# simplePDschematicsv1.net
KiCad netlist of a schematic drawn in EAGLE
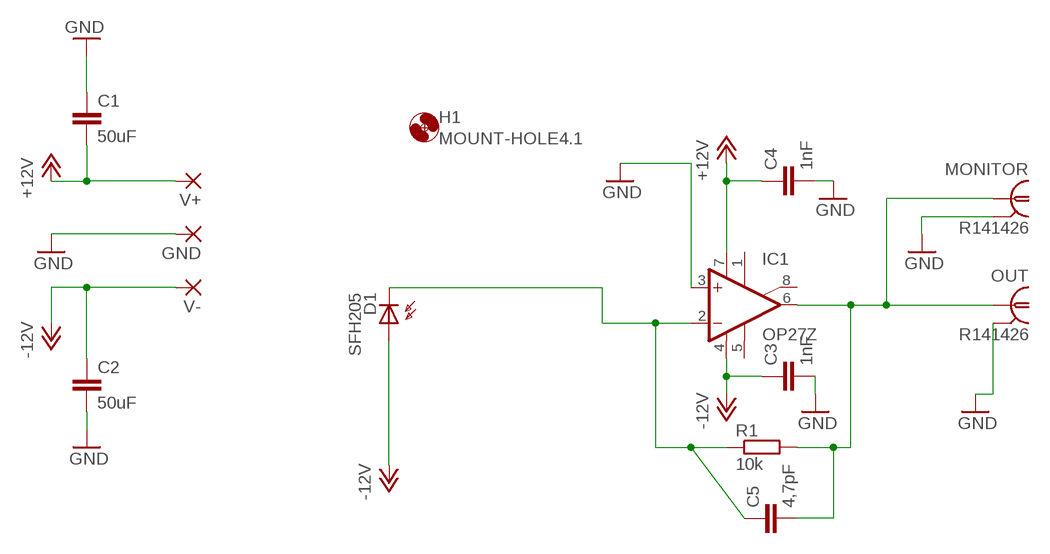
[diagram p0: schematic, sheet 1]

(export (version "E")
  (design (tool "Eeschema 10.0.6"))
  (components
    (comp (ref "C1")
      (value "50uF")
      (footprint "eagle-import:C025-050X050")
      (libsource (lib "eagle-import") (part "C-EU025-050X050"))
    )
    (comp (ref "C2")
      (value "50uF")
      (footprint "eagle-import:C025-050X050")
      (libsource (lib "eagle-import") (part "C-EU025-050X050"))
    )
    (comp (ref "C3")
      (value "1nF")
      (footprint "eagle-import:C025-050X050")
      (libsource (lib "eagle-import") (part "C-EU025-050X050"))
    )
    (comp (ref "C4")
      (value "1nF")
      (footprint "eagle-import:C025-050X050")
      (libsource (lib "eagle-import") (part "C-EU025-050X050"))
    )
    (comp (ref "C5")
      (value "4,7pF")
      (footprint "eagle-import:C025-050X050")
      (libsource (lib "eagle-import") (part "C-EU025-050X050"))
    )
    (comp (ref "D1")
      (value "SFH205")
      (footprint "eagle-import:SFH205")
      (libsource (lib "eagle-import") (part "SFH205"))
    )
    (comp (ref "GND")
      (value "1,6/0,9")
      (footprint "eagle-import:1,6_0,9")
      (libsource (lib "eagle-import") (part "1,6/0,9"))
    )
    (comp (ref "H1")
      (value "MOUNT-HOLE4.1")
      (footprint "eagle-import:4,1")
      (libsource (lib "eagle-import") (part "MOUNT-HOLE4.1"))
    )
    (comp (ref "IC1")
      (value "OP27Z")
      (footprint "eagle-import:DIL08")
      (libsource (lib "eagle-import") (part "OP27Z"))
    )
    (comp (ref "MONITOR")
      (value "R141426")
      (footprint "eagle-import:R141426")
      (fields (field (name "MF") "FARNELL") (field (name "MPN") "R141426161"))
      (libsource (lib "eagle-import") (part "R141426"))
    )
    (comp (ref "OUT")
      (value "R141426")
      (footprint "eagle-import:R141426")
      (fields (field (name "MF") "FARNELL") (field (name "MPN") "R141426161"))
      (libsource (lib "eagle-import") (part "R141426"))
    )
    (comp (ref "R1")
      (value "10k")
      (footprint "eagle-import:0207_5V")
      (libsource (lib "eagle-import") (part "R-EU_0207/5V"))
    )
    (comp (ref "V+")
      (value "1,6/0,9")
      (footprint "eagle-import:1,6_0,9")
      (libsource (lib "eagle-import") (part "1,6/0,9"))
    )
    (comp (ref "V-")
      (value "1,6/0,9")
      (footprint "eagle-import:1,6_0,9")
      (libsource (lib "eagle-import") (part "1,6/0,9"))
    )
  )
  (nets
    (net (code "1") (name "+12V") (class "Default")
      (node (ref "C1") (pin "2") (pinfunction "2_2") (pintype "passive"))
      (node (ref "C4") (pin "1") (pinfunction "1_1") (pintype "passive"))
      (node (ref "IC1") (pin "7") (pinfunction "V+_7") (pintype "power_in"))
      (node (ref "V+") (pin "1") (pinfunction "P_1") (pintype "passive"))
    )
    (net (code "2") (name "-12V") (class "Default")
      (node (ref "C2") (pin "1") (pinfunction "1_1") (pintype "passive"))
      (node (ref "C3") (pin "1") (pinfunction "1_1") (pintype "passive"))
      (node (ref "D1") (pin "A") (pinfunction "A_A") (pintype "passive"))
      (node (ref "IC1") (pin "4") (pinfunction "V-_4") (pintype "power_in"))
      (node (ref "V-") (pin "1") (pinfunction "P_1") (pintype "passive"))
    )
    (net (code "3") (name "GND") (class "Default")
      (node (ref "C1") (pin "1") (pinfunction "1_1") (pintype "passive"))
      (node (ref "C2") (pin "2") (pinfunction "2_2") (pintype "passive"))
      (node (ref "C3") (pin "2") (pinfunction "2_2") (pintype "passive"))
      (node (ref "C4") (pin "2") (pinfunction "2_2") (pintype "passive"))
      (node (ref "GND") (pin "1") (pinfunction "P_1") (pintype "passive"))
      (node (ref "IC1") (pin "3") (pinfunction "+IN_3") (pintype "input"))
      (node (ref "MONITOR") (pin "2") (pinfunction "2_2") (pintype "passive"))
      (node (ref "MONITOR") (pin "3") (pinfunction "2_3") (pintype "passive"))
      (node (ref "MONITOR") (pin "4") (pinfunction "2_4") (pintype "passive"))
      (node (ref "MONITOR") (pin "5") (pinfunction "2_5") (pintype "passive"))
      (node (ref "OUT") (pin "2") (pinfunction "2_2") (pintype "passive"))
      (node (ref "OUT") (pin "3") (pinfunction "2_3") (pintype "passive"))
      (node (ref "OUT") (pin "4") (pinfunction "2_4") (pintype "passive"))
      (node (ref "OUT") (pin "5") (pinfunction "2_5") (pintype "passive"))
    )
    (net (code "4") (name "Net-(D1-C)") (class "Default")
      (node (ref "C5") (pin "1") (pinfunction "1_1") (pintype "passive"))
      (node (ref "D1") (pin "K") (pinfunction "C_K") (pintype "passive"))
      (node (ref "IC1") (pin "2") (pinfunction "-IN_2") (pintype "input"))
      (node (ref "R1") (pin "1") (pinfunction "1_1") (pintype "passive"))
    )
    (net (code "5") (name "Net-(IC1-OUT)") (class "Default")
      (node (ref "C5") (pin "2") (pinfunction "2_2") (pintype "passive"))
      (node (ref "IC1") (pin "6") (pinfunction "OUT_6") (pintype "output"))
      (node (ref "MONITOR") (pin "1") (pinfunction "1_1") (pintype "passive"))
      (node (ref "OUT") (pin "1") (pinfunction "1_1") (pintype "passive"))
      (node (ref "R1") (pin "2") (pinfunction "2_2") (pintype "passive"))
    )
    (net (code "6") (name "unconnected-(IC1-ON1-Pad1)") (class "Default")
      (node (ref "IC1") (pin "1") (pinfunction "ON1_1") (pintype "passive"))
    )
    (net (code "7") (name "unconnected-(IC1-ON2-Pad8)") (class "Default")
      (node (ref "IC1") (pin "8") (pinfunction "ON2_8") (pintype "passive"))
    )
    (net (code "8") (name "unconnected-(IC1-OPT-Pad5)") (class "Default")
      (node (ref "IC1") (pin "5") (pinfunction "OPT_5") (pintype "passive"))
    )
  )
)
